# Sheet1.net
KiCad netlist of a schematic drawn in Altium Designer
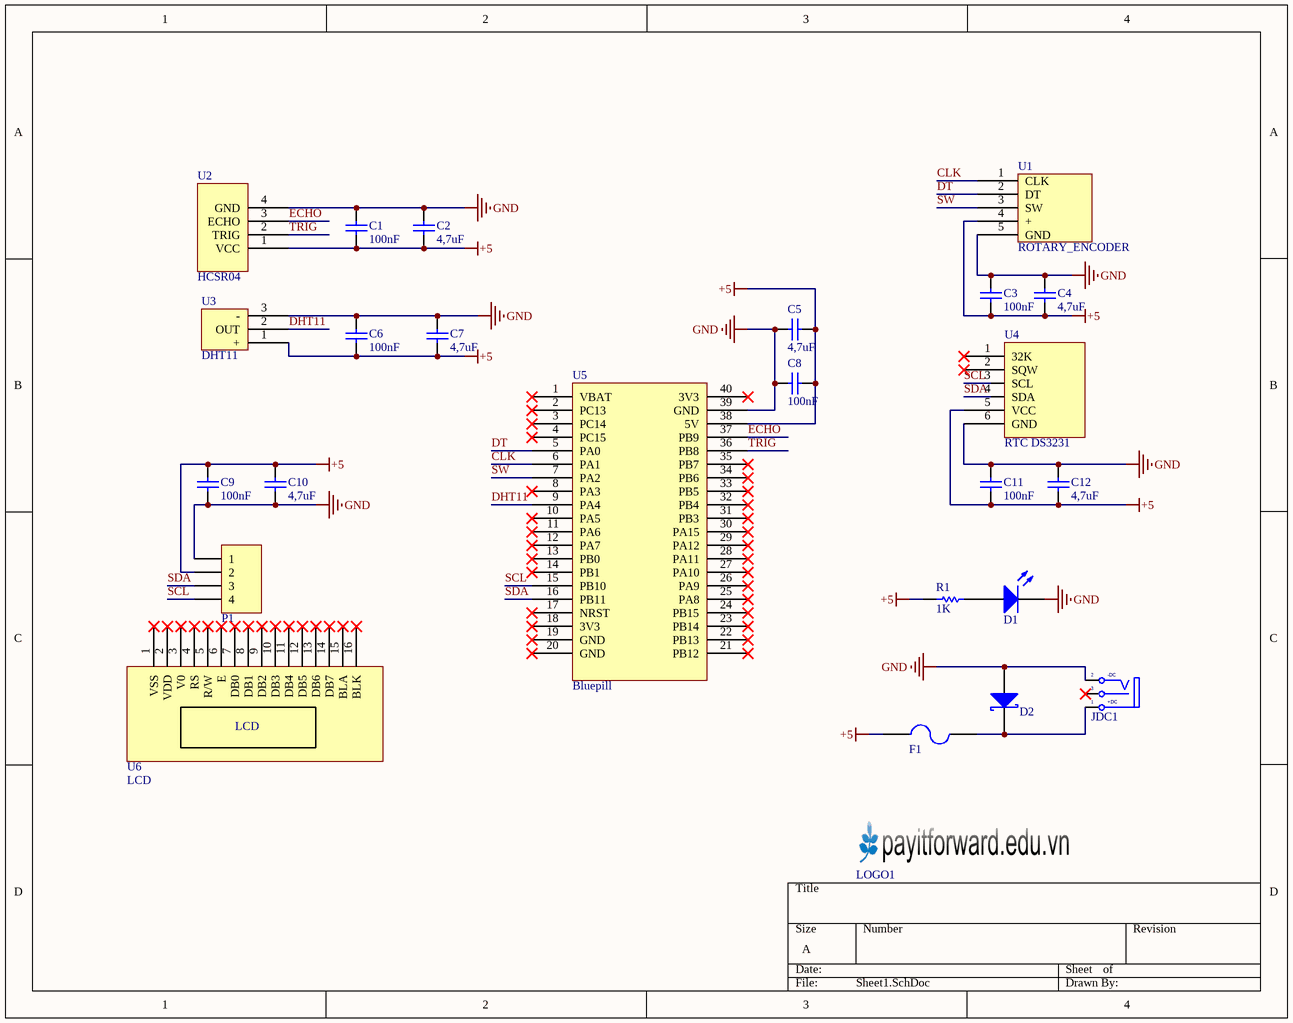
[diagram p0: Sheet1.SchDoc]

(export (version "E")
  (design (tool "Eeschema 10.0.6"))
  (components
    (comp (ref "C1")
      (value "100nF")
      (footprint "CAP-SM-0805")
      (description "Capacitor")
      (fields (field (name "Comment") "Cap Non-Pol SMD"))
      (libsource (lib "PIF_Library") (part "Cap Non-Pol SMD"))
    )
    (comp (ref "C2")
      (value "4,7uF")
      (footprint "CAP-SM-0805")
      (description "Capacitor")
      (fields (field (name "Comment") "Cap Non-Pol SMD"))
      (libsource (lib "PIF_Library") (part "Cap Non-Pol SMD"))
    )
    (comp (ref "C3")
      (value "100nF")
      (footprint "CAP-SM-0805")
      (description "Capacitor")
      (fields (field (name "Comment") "Cap Non-Pol SMD"))
      (libsource (lib "PIF_Library") (part "Cap Non-Pol SMD"))
    )
    (comp (ref "C4")
      (value "4,7uF")
      (footprint "CAP-SM-0805")
      (description "Capacitor")
      (fields (field (name "Comment") "Cap Non-Pol SMD"))
      (libsource (lib "PIF_Library") (part "Cap Non-Pol SMD"))
    )
    (comp (ref "C5")
      (value "4,7uF")
      (footprint "CAP-SM-0805")
      (description "Capacitor")
      (fields (field (name "Comment") "Cap Non-Pol SMD"))
      (libsource (lib "PIF_Library") (part "Cap Non-Pol SMD"))
    )
    (comp (ref "C6")
      (value "100nF")
      (footprint "CAP-SM-0805")
      (description "Capacitor")
      (fields (field (name "Comment") "Cap Non-Pol SMD"))
      (libsource (lib "PIF_Library") (part "Cap Non-Pol SMD"))
    )
    (comp (ref "C7")
      (value "4,7uF")
      (footprint "CAP-SM-0805")
      (description "Capacitor")
      (fields (field (name "Comment") "Cap Non-Pol SMD"))
      (libsource (lib "PIF_Library") (part "Cap Non-Pol SMD"))
    )
    (comp (ref "C8")
      (value "100nF")
      (footprint "CAP-SM-0805")
      (description "Capacitor")
      (fields (field (name "Comment") "Cap Non-Pol SMD"))
      (libsource (lib "PIF_Library") (part "Cap Non-Pol SMD"))
    )
    (comp (ref "C9")
      (value "100nF")
      (footprint "CAP-SM-0805")
      (description "Capacitor")
      (fields (field (name "Comment") "Cap Non-Pol SMD"))
      (libsource (lib "PIF_Library") (part "Cap Non-Pol SMD"))
    )
    (comp (ref "C10")
      (value "4,7uF")
      (footprint "CAP-SM-0805")
      (description "Capacitor")
      (fields (field (name "Comment") "Cap Non-Pol SMD"))
      (libsource (lib "PIF_Library") (part "Cap Non-Pol SMD"))
    )
    (comp (ref "C11")
      (value "100nF")
      (footprint "CAP-SM-0805")
      (description "Capacitor")
      (fields (field (name "Comment") "Cap Non-Pol SMD"))
      (libsource (lib "PIF_Library") (part "Cap Non-Pol SMD"))
    )
    (comp (ref "C12")
      (value "4,7uF")
      (footprint "CAP-SM-0805")
      (description "Capacitor")
      (fields (field (name "Comment") "Cap Non-Pol SMD"))
      (libsource (lib "PIF_Library") (part "Cap Non-Pol SMD"))
    )
    (comp (ref "D1") (value "LED") (footprint "LED-3mm") (libsource (lib "PIF_Library") (part "LED")))
    (comp (ref "D2")
      (value "D Schottky")
      (footprint "SS34")
      (description "Schottky Diode")
      (fields (field (name "PUBLISHER") "Altium Limited"))
      (libsource (lib "PIF_Library") (part "D Schottky"))
    )
    (comp (ref "F1") (value "Fuse") (footprint "FUSE SMD") (libsource (lib "PIF_Library") (part "Fuse")))
    (comp (ref "JDC1")
      (value "Jack DC")
      (footprint "DC-IN")
      (description "Jack DC input")
      (libsource (lib "PIF_Library") (part "Jack DC"))
    )
    (comp (ref "LOGO1")
      (value "LOGO PIF")
      (footprint "PIF LOGO BIG TOP")
      (libsource (lib "PIF_Library") (part "LOGO PIF"))
    )
    (comp (ref "P1")
      (value "Header 4H")
      (footprint "JP4H")
      (description "Header, 4-Pin, Right Angle")
      (fields (field (name "PUBLISHER") "Altium Limited"))
      (libsource (lib "PIF_Library") (part "Header 4H"))
    )
    (comp (ref "R1")
      (value "1K")
      (footprint "RES-SM-0805")
      (description "Resistor")
      (fields (field (name "Comment") "RESISTOR SMD"))
      (libsource (lib "PIF_Library") (part "RESISTOR SMD"))
    )
    (comp (ref "U1")
      (value "ROTARY_ENCODER")
      (footprint "ROTARY_ENCODER")
      (libsource (lib "_PIFProject_LibPCB_TuanPham_v1-01") (part "ROTARY_ENCODER"))
    )
    (comp (ref "U2")
      (value "HCSR04")
      (footprint "HCSR04")
      (libsource (lib "_PIFProject_LibPCB_TuanPham_v1-01") (part "HCSR04"))
    )
    (comp (ref "U3")
      (value "DHT11")
      (footprint "DHT11")
      (libsource (lib "_PIFProject_LibPCB_TuanPham_v1-01") (part "DHT11"))
    )
    (comp (ref "U4")
      (value "RTC DS3231")
      (footprint "RTC_DS3231")
      (libsource (lib "_PIFProject_LibPCB_TuanPham_v1-01") (part "RTC DS3231"))
    )
    (comp (ref "U5")
      (value "Bluepill")
      (footprint "STM32F103C8T6")
      (libsource (lib "_PIFProject_LibPCB_TuanPham_v1-01") (part "STM32F103C8T6"))
    )
    (comp (ref "U6")
      (value "LCD")
      (footprint "LCD 2004")
      (libsource (lib "_PIFProject_LibPCB_TuanPham_v1-01") (part "LCD"))
    )
  )
  (nets
    (net (code "1") (name "+5") (class "Default")
      (node (ref "C1") (pin "1") (pinfunction "1_1") (pintype "passive"))
      (node (ref "C10") (pin "2") (pinfunction "2_2") (pintype "passive"))
      (node (ref "C11") (pin "2") (pinfunction "2_2") (pintype "passive"))
      (node (ref "C12") (pin "2") (pinfunction "2_2") (pintype "passive"))
      (node (ref "C2") (pin "1") (pinfunction "1_1") (pintype "passive"))
      (node (ref "C3") (pin "2") (pinfunction "2_2") (pintype "passive"))
      (node (ref "C4") (pin "2") (pinfunction "2_2") (pintype "passive"))
      (node (ref "C5") (pin "1") (pinfunction "1_1") (pintype "passive"))
      (node (ref "C6") (pin "1") (pinfunction "1_1") (pintype "passive"))
      (node (ref "C7") (pin "1") (pinfunction "1_1") (pintype "passive"))
      (node (ref "C8") (pin "1") (pinfunction "1_1") (pintype "passive"))
      (node (ref "C9") (pin "2") (pinfunction "2_2") (pintype "passive"))
      (node (ref "F1") (pin "1") (pinfunction "1_1") (pintype "passive"))
      (node (ref "P1") (pin "2") (pinfunction "2_2") (pintype "passive"))
      (node (ref "R1") (pin "1") (pinfunction "1_1") (pintype "passive"))
      (node (ref "U1") (pin "4") (pinfunction "+_4") (pintype "passive"))
      (node (ref "U2") (pin "1") (pinfunction "VCC_1") (pintype "passive"))
      (node (ref "U3") (pin "1") (pinfunction "+_1") (pintype "passive"))
      (node (ref "U4") (pin "5") (pinfunction "VCC_5") (pintype "passive"))
      (node (ref "U5") (pin "38") (pinfunction "5V_38") (pintype "passive"))
    )
    (net (code "2") (name "/CLK") (class "Default")
      (node (ref "U1") (pin "1") (pinfunction "CLK_1") (pintype "passive"))
      (node (ref "U5") (pin "6") (pinfunction "PA1_6") (pintype "passive"))
    )
    (net (code "3") (name "/DHT11") (class "Default")
      (node (ref "U3") (pin "2") (pinfunction "OUT_2") (pintype "passive"))
      (node (ref "U5") (pin "9") (pinfunction "PA4_9") (pintype "passive"))
    )
    (net (code "4") (name "/DT") (class "Default")
      (node (ref "U1") (pin "2") (pinfunction "DT_2") (pintype "passive"))
      (node (ref "U5") (pin "5") (pinfunction "PA0_5") (pintype "passive"))
    )
    (net (code "5") (name "/ECHO") (class "Default")
      (node (ref "U2") (pin "3") (pinfunction "ECHO_3") (pintype "passive"))
      (node (ref "U5") (pin "37") (pinfunction "PB9_37") (pintype "passive"))
    )
    (net (code "6") (name "/SCL") (class "Default")
      (node (ref "P1") (pin "4") (pinfunction "4_4") (pintype "passive"))
      (node (ref "U4") (pin "3") (pinfunction "SCL_3") (pintype "passive"))
      (node (ref "U5") (pin "15") (pinfunction "PB10_15") (pintype "passive"))
    )
    (net (code "7") (name "/SDA") (class "Default")
      (node (ref "P1") (pin "3") (pinfunction "3_3") (pintype "passive"))
      (node (ref "U4") (pin "4") (pinfunction "SDA_4") (pintype "passive"))
      (node (ref "U5") (pin "16") (pinfunction "PB11_16") (pintype "passive"))
    )
    (net (code "8") (name "/SW") (class "Default")
      (node (ref "U1") (pin "3") (pinfunction "SW_3") (pintype "passive"))
      (node (ref "U5") (pin "7") (pinfunction "PA2_7") (pintype "passive"))
    )
    (net (code "9") (name "/TRIG") (class "Default")
      (node (ref "U2") (pin "2") (pinfunction "TRIG_2") (pintype "passive"))
      (node (ref "U5") (pin "36") (pinfunction "PB8_36") (pintype "passive"))
    )
    (net (code "10") (name "GND") (class "Default")
      (node (ref "C1") (pin "2") (pinfunction "2_2") (pintype "passive"))
      (node (ref "C10") (pin "1") (pinfunction "1_1") (pintype "passive"))
      (node (ref "C11") (pin "1") (pinfunction "1_1") (pintype "passive"))
      (node (ref "C12") (pin "1") (pinfunction "1_1") (pintype "passive"))
      (node (ref "C2") (pin "2") (pinfunction "2_2") (pintype "passive"))
      (node (ref "C3") (pin "1") (pinfunction "1_1") (pintype "passive"))
      (node (ref "C4") (pin "1") (pinfunction "1_1") (pintype "passive"))
      (node (ref "C5") (pin "2") (pinfunction "2_2") (pintype "passive"))
      (node (ref "C6") (pin "2") (pinfunction "2_2") (pintype "passive"))
      (node (ref "C7") (pin "2") (pinfunction "2_2") (pintype "passive"))
      (node (ref "C8") (pin "2") (pinfunction "2_2") (pintype "passive"))
      (node (ref "C9") (pin "1") (pinfunction "1_1") (pintype "passive"))
      (node (ref "D1") (pin "2") (pinfunction "K_2") (pintype "passive"))
      (node (ref "D2") (pin "1") (pinfunction "A_1") (pintype "passive"))
      (node (ref "JDC1") (pin "2") (pinfunction "TN_2") (pintype "passive"))
      (node (ref "P1") (pin "1") (pinfunction "1_1") (pintype "passive"))
      (node (ref "U1") (pin "5") (pinfunction "GND_5") (pintype "passive"))
      (node (ref "U2") (pin "4") (pinfunction "GND_4") (pintype "passive"))
      (node (ref "U3") (pin "3") (pinfunction "-_3") (pintype "passive"))
      (node (ref "U4") (pin "6") (pinfunction "GND_6") (pintype "passive"))
      (node (ref "U5") (pin "39") (pinfunction "GND_39") (pintype "passive"))
    )
    (net (code "11") (name "Net-(D1-A)") (class "Default")
      (node (ref "D1") (pin "1") (pinfunction "A_1") (pintype "passive"))
      (node (ref "R1") (pin "2") (pinfunction "2_2") (pintype "passive"))
    )
    (net (code "12") (name "Net-(D2-K)") (class "Default")
      (node (ref "D2") (pin "2") (pinfunction "K_2") (pintype "passive"))
      (node (ref "F1") (pin "2") (pinfunction "2_2") (pintype "passive"))
      (node (ref "JDC1") (pin "1") (pinfunction "T_1") (pintype "passive"))
    )
    (net (code "13") (name "unconnected-(JDC1-S-Pad3)") (class "Default")
      (node (ref "JDC1") (pin "3") (pinfunction "S_3") (pintype "power_in+no_connect"))
    )
    (net (code "14") (name "unconnected-(U4-32K-Pad1)") (class "Default")
      (node (ref "U4") (pin "1") (pinfunction "32K_1") (pintype "passive+no_connect"))
    )
    (net (code "15") (name "unconnected-(U4-SQW-Pad2)") (class "Default")
      (node (ref "U4") (pin "2") (pinfunction "SQW_2") (pintype "passive+no_connect"))
    )
    (net (code "16") (name "unconnected-(U5-3V3-Pad18)") (class "Default")
      (node (ref "U5") (pin "18") (pinfunction "3V3_18") (pintype "passive+no_connect"))
    )
    (net (code "17") (name "unconnected-(U5-3V3-Pad40)") (class "Default")
      (node (ref "U5") (pin "40") (pinfunction "3V3_40") (pintype "passive+no_connect"))
    )
    (net (code "18") (name "unconnected-(U5-GND-Pad19)") (class "Default")
      (node (ref "U5") (pin "19") (pinfunction "GND_19") (pintype "passive+no_connect"))
    )
    (net (code "19") (name "unconnected-(U5-GND-Pad20)") (class "Default")
      (node (ref "U5") (pin "20") (pinfunction "GND_20") (pintype "passive+no_connect"))
    )
    (net (code "20") (name "unconnected-(U5-NRST-Pad17)") (class "Default")
      (node (ref "U5") (pin "17") (pinfunction "NRST_17") (pintype "passive+no_connect"))
    )
    (net (code "21") (name "unconnected-(U5-PA3-Pad8)") (class "Default")
      (node (ref "U5") (pin "8") (pinfunction "PA3_8") (pintype "passive+no_connect"))
    )
    (net (code "22") (name "unconnected-(U5-PA5-Pad10)") (class "Default")
      (node (ref "U5") (pin "10") (pinfunction "PA5_10") (pintype "passive+no_connect"))
    )
    (net (code "23") (name "unconnected-(U5-PA6-Pad11)") (class "Default")
      (node (ref "U5") (pin "11") (pinfunction "PA6_11") (pintype "passive+no_connect"))
    )
    (net (code "24") (name "unconnected-(U5-PA7-Pad12)") (class "Default")
      (node (ref "U5") (pin "12") (pinfunction "PA7_12") (pintype "passive+no_connect"))
    )
    (net (code "25") (name "unconnected-(U5-PA8-Pad25)") (class "Default")
      (node (ref "U5") (pin "25") (pinfunction "PA8_25") (pintype "passive+no_connect"))
    )
    (net (code "26") (name "unconnected-(U5-PA9-Pad26)") (class "Default")
      (node (ref "U5") (pin "26") (pinfunction "PA9_26") (pintype "passive+no_connect"))
    )
    (net (code "27") (name "unconnected-(U5-PA10-Pad27)") (class "Default")
      (node (ref "U5") (pin "27") (pinfunction "PA10_27") (pintype "passive+no_connect"))
    )
    (net (code "28") (name "unconnected-(U5-PA11-Pad28)") (class "Default")
      (node (ref "U5") (pin "28") (pinfunction "PA11_28") (pintype "passive+no_connect"))
    )
    (net (code "29") (name "unconnected-(U5-PA12-Pad29)") (class "Default")
      (node (ref "U5") (pin "29") (pinfunction "PA12_29") (pintype "passive+no_connect"))
    )
    (net (code "30") (name "unconnected-(U5-PA15-Pad30)") (class "Default")
      (node (ref "U5") (pin "30") (pinfunction "PA15_30") (pintype "passive+no_connect"))
    )
    (net (code "31") (name "unconnected-(U5-PB0-Pad13)") (class "Default")
      (node (ref "U5") (pin "13") (pinfunction "PB0_13") (pintype "passive+no_connect"))
    )
    (net (code "32") (name "unconnected-(U5-PB1-Pad14)") (class "Default")
      (node (ref "U5") (pin "14") (pinfunction "PB1_14") (pintype "passive+no_connect"))
    )
    (net (code "33") (name "unconnected-(U5-PB3-Pad31)") (class "Default")
      (node (ref "U5") (pin "31") (pinfunction "PB3_31") (pintype "passive+no_connect"))
    )
    (net (code "34") (name "unconnected-(U5-PB4-Pad32)") (class "Default")
      (node (ref "U5") (pin "32") (pinfunction "PB4_32") (pintype "passive+no_connect"))
    )
    (net (code "35") (name "unconnected-(U5-PB5-Pad33)") (class "Default")
      (node (ref "U5") (pin "33") (pinfunction "PB5_33") (pintype "passive+no_connect"))
    )
    (net (code "36") (name "unconnected-(U5-PB6-Pad34)") (class "Default")
      (node (ref "U5") (pin "34") (pinfunction "PB6_34") (pintype "passive+no_connect"))
    )
    (net (code "37") (name "unconnected-(U5-PB7-Pad35)") (class "Default")
      (node (ref "U5") (pin "35") (pinfunction "PB7_35") (pintype "passive+no_connect"))
    )
    (net (code "38") (name "unconnected-(U5-PB12-Pad21)") (class "Default")
      (node (ref "U5") (pin "21") (pinfunction "PB12_21") (pintype "passive+no_connect"))
    )
    (net (code "39") (name "unconnected-(U5-PB13-Pad22)") (class "Default")
      (node (ref "U5") (pin "22") (pinfunction "PB13_22") (pintype "passive+no_connect"))
    )
    (net (code "40") (name "unconnected-(U5-PB14-Pad23)") (class "Default")
      (node (ref "U5") (pin "23") (pinfunction "PB14_23") (pintype "passive+no_connect"))
    )
    (net (code "41") (name "unconnected-(U5-PB15-Pad24)") (class "Default")
      (node (ref "U5") (pin "24") (pinfunction "PB15_24") (pintype "passive+no_connect"))
    )
    (net (code "42") (name "unconnected-(U5-PC13-Pad2)") (class "Default")
      (node (ref "U5") (pin "2") (pinfunction "PC13_2") (pintype "passive+no_connect"))
    )
    (net (code "43") (name "unconnected-(U5-PC14-Pad3)") (class "Default")
      (node (ref "U5") (pin "3") (pinfunction "PC14_3") (pintype "passive+no_connect"))
    )
    (net (code "44") (name "unconnected-(U5-PC15-Pad4)") (class "Default")
      (node (ref "U5") (pin "4") (pinfunction "PC15_4") (pintype "passive+no_connect"))
    )
    (net (code "45") (name "unconnected-(U5-VBAT-Pad1)") (class "Default")
      (node (ref "U5") (pin "1") (pinfunction "VBAT_1") (pintype "passive+no_connect"))
    )
    (net (code "46") (name "unconnected-(U6-BLA-Pad15)") (class "Default")
      (node (ref "U6") (pin "15") (pinfunction "BLA_15") (pintype "passive+no_connect"))
    )
    (net (code "47") (name "unconnected-(U6-BLK-Pad16)") (class "Default")
      (node (ref "U6") (pin "16") (pinfunction "BLK_16") (pintype "passive+no_connect"))
    )
    (net (code "48") (name "unconnected-(U6-DB0-Pad7)") (class "Default")
      (node (ref "U6") (pin "7") (pinfunction "DB0_7") (pintype "passive+no_connect"))
    )
    (net (code "49") (name "unconnected-(U6-DB1-Pad8)") (class "Default")
      (node (ref "U6") (pin "8") (pinfunction "DB1_8") (pintype "passive+no_connect"))
    )
    (net (code "50") (name "unconnected-(U6-DB2-Pad9)") (class "Default")
      (node (ref "U6") (pin "9") (pinfunction "DB2_9") (pintype "passive+no_connect"))
    )
    (net (code "51") (name "unconnected-(U6-DB3-Pad10)") (class "Default")
      (node (ref "U6") (pin "10") (pinfunction "DB3_10") (pintype "passive+no_connect"))
    )
    (net (code "52") (name "unconnected-(U6-DB4-Pad11)") (class "Default")
      (node (ref "U6") (pin "11") (pinfunction "DB4_11") (pintype "passive+no_connect"))
    )
    (net (code "53") (name "unconnected-(U6-DB5-Pad12)") (class "Default")
      (node (ref "U6") (pin "12") (pinfunction "DB5_12") (pintype "passive+no_connect"))
    )
    (net (code "54") (name "unconnected-(U6-DB6-Pad13)") (class "Default")
      (node (ref "U6") (pin "13") (pinfunction "DB6_13") (pintype "passive+no_connect"))
    )
    (net (code "55") (name "unconnected-(U6-DB7-Pad14)") (class "Default")
      (node (ref "U6") (pin "14") (pinfunction "DB7_14") (pintype "passive+no_connect"))
    )
    (net (code "56") (name "unconnected-(U6-E-Pad6)") (class "Default")
      (node (ref "U6") (pin "6") (pinfunction "E_6") (pintype "passive+no_connect"))
    )
    (net (code "57") (name "unconnected-(U6-RS-Pad4)") (class "Default")
      (node (ref "U6") (pin "4") (pinfunction "RS_4") (pintype "passive+no_connect"))
    )
    (net (code "58") (name "unconnected-(U6-R{slash}W-Pad5)") (class "Default")
      (node (ref "U6") (pin "5") (pinfunction "R/W_5") (pintype "passive+no_connect"))
    )
    (net (code "59") (name "unconnected-(U6-V0-Pad3)") (class "Default")
      (node (ref "U6") (pin "3") (pinfunction "V0_3") (pintype "passive+no_connect"))
    )
    (net (code "60") (name "unconnected-(U6-VDD-Pad2)") (class "Default")
      (node (ref "U6") (pin "2") (pinfunction "VDD_2") (pintype "passive+no_connect"))
    )
    (net (code "61") (name "unconnected-(U6-VSS-Pad1)") (class "Default")
      (node (ref "U6") (pin "1") (pinfunction "VSS_1") (pintype "passive+no_connect"))
    )
  )
)
